# Decoder.net
KiCad netlist of a schematic drawn in EAGLE
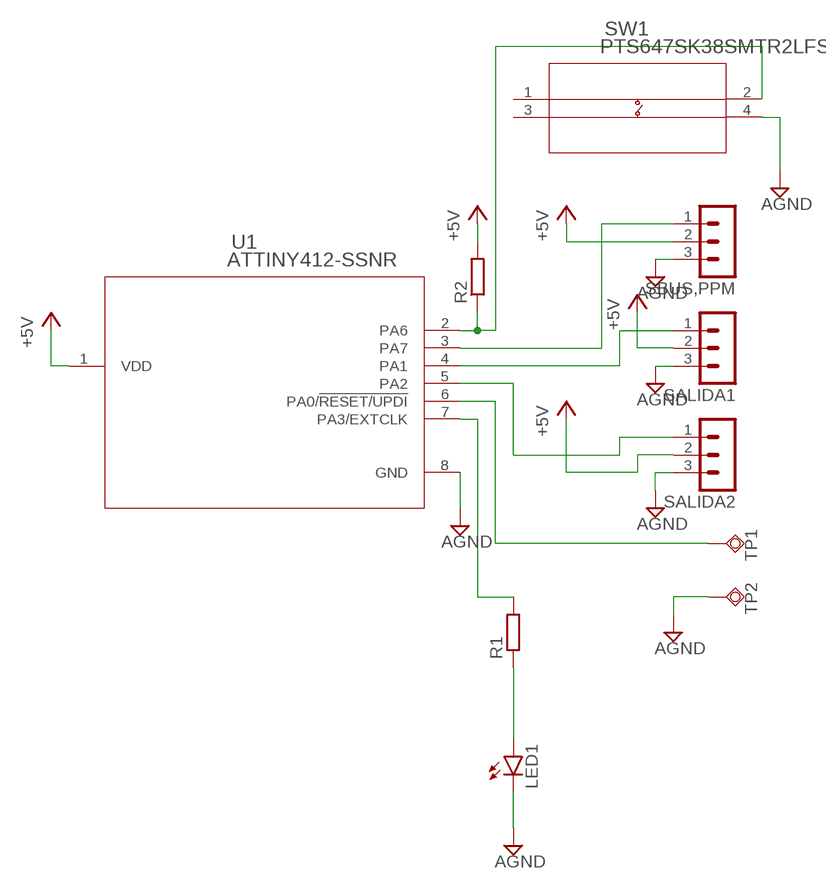
[diagram p0: schematic, sheet 1]

(export (version "E")
  (design (tool "Eeschema 10.0.6"))
  (components
    (comp (ref "LED1")
      (value "LEDCHIPLED_0603")
      (footprint "eagle-import:CHIPLED_0603")
      (libsource (lib "eagle-import") (part "LEDCHIPLED_0603"))
    )
    (comp (ref "R1")
      (value "R-EU_R0805")
      (footprint "eagle-import:R0805")
      (libsource (lib "eagle-import") (part "R-EU_R0805"))
    )
    (comp (ref "R2")
      (value "R-EU_R0805")
      (footprint "eagle-import:R0805")
      (libsource (lib "eagle-import") (part "R-EU_R0805"))
    )
    (comp (ref "SALIDA1")
      (value "MA03-1")
      (footprint "eagle-import:MA03-1")
      (libsource (lib "eagle-import") (part "MA03-1"))
    )
    (comp (ref "SALIDA2")
      (value "MA03-1")
      (footprint "eagle-import:MA03-1")
      (libsource (lib "eagle-import") (part "MA03-1"))
    )
    (comp (ref "SBUS,PPM")
      (value "MA03-1")
      (footprint "eagle-import:MA03-1")
      (libsource (lib "eagle-import") (part "MA03-1"))
    )
    (comp (ref "SW1")
      (value "PTS647SK38SMTR2LFS")
      (footprint "eagle-import:PTS647SK38SMTR2LFS_CNK")
      (fields (field (name "COPYRIGHT") "Copyright (C) 2018 Accelerated Designs. All rights reserved"))
      (libsource (lib "eagle-import") (part "PTS647SK38SMTR2LFS"))
    )
    (comp (ref "TP1")
      (value "TPSQTP13R")
      (footprint "eagle-import:TP13R")
      (libsource (lib "eagle-import") (part "TPSQTP13R"))
    )
    (comp (ref "TP2")
      (value "TPSQTP13R")
      (footprint "eagle-import:TP13R")
      (libsource (lib "eagle-import") (part "TPSQTP13R"))
    )
    (comp (ref "U1")
      (value "ATTINY412-SSNR")
      (footprint "eagle-import:SOIC8_SA_SST_MCH")
      (fields (field (name "COPYRIGHT") "Copyright (C) 2018 Accelerated Designs. All rights reserved"))
      (libsource (lib "eagle-import") (part "ATTINY412-SSNR"))
    )
  )
  (nets
    (net (code "1") (name "+5V") (class "Default")
      (node (ref "R2") (pin "2") (pinfunction "2_2") (pintype "passive"))
      (node (ref "SALIDA1") (pin "2") (pinfunction "2_2") (pintype "passive"))
      (node (ref "SALIDA2") (pin "2") (pinfunction "2_2") (pintype "passive"))
      (node (ref "SBUS,PPM") (pin "2") (pinfunction "2_2") (pintype "passive"))
      (node (ref "U1") (pin "1") (pinfunction "VDD_1") (pintype "power_in"))
    )
    (net (code "2") (name "AGND") (class "Default")
      (node (ref "LED1") (pin "C") (pinfunction "C_C") (pintype "passive"))
      (node (ref "SALIDA1") (pin "3") (pinfunction "3_3") (pintype "passive"))
      (node (ref "SALIDA2") (pin "3") (pinfunction "3_3") (pintype "passive"))
      (node (ref "SBUS,PPM") (pin "3") (pinfunction "3_3") (pintype "passive"))
      (node (ref "SW1") (pin "4") (pinfunction "4_4") (pintype "passive"))
      (node (ref "TP2") (pin "TP") (pinfunction "TP_TP") (pintype "input"))
      (node (ref "U1") (pin "8") (pinfunction "GND_8") (pintype "passive"))
    )
    (net (code "3") (name "Net-(LED1-PadA)") (class "Default")
      (node (ref "LED1") (pin "A") (pinfunction "A_A") (pintype "passive"))
      (node (ref "R1") (pin "1") (pinfunction "1_1") (pintype "passive"))
    )
    (net (code "4") (name "Net-(U1-PA0{slash}~{RESET{slash}UPDI})") (class "Default")
      (node (ref "TP1") (pin "TP") (pinfunction "TP_TP") (pintype "input"))
      (node (ref "U1") (pin "6") (pinfunction "PA0/~{RESET/UPDI}_6") (pintype "bidirectional"))
    )
    (net (code "5") (name "Net-(U1-PA1)") (class "Default")
      (node (ref "SALIDA1") (pin "1") (pinfunction "1_1") (pintype "passive"))
      (node (ref "U1") (pin "4") (pinfunction "PA1_4") (pintype "bidirectional"))
    )
    (net (code "6") (name "Net-(U1-PA2)") (class "Default")
      (node (ref "SALIDA2") (pin "1") (pinfunction "1_1") (pintype "passive"))
      (node (ref "U1") (pin "5") (pinfunction "PA2_5") (pintype "bidirectional"))
    )
    (net (code "7") (name "Net-(U1-PA3{slash}EXTCLK)") (class "Default")
      (node (ref "R1") (pin "2") (pinfunction "2_2") (pintype "passive"))
      (node (ref "U1") (pin "7") (pinfunction "PA3/EXTCLK_7") (pintype "bidirectional"))
    )
    (net (code "8") (name "Net-(U1-PA6)") (class "Default")
      (node (ref "R2") (pin "1") (pinfunction "1_1") (pintype "passive"))
      (node (ref "SW1") (pin "2") (pinfunction "2_2") (pintype "passive"))
      (node (ref "U1") (pin "2") (pinfunction "PA6_2") (pintype "bidirectional"))
    )
    (net (code "9") (name "Net-(U1-PA7)") (class "Default")
      (node (ref "SBUS,PPM") (pin "1") (pinfunction "1_1") (pintype "passive"))
      (node (ref "U1") (pin "3") (pinfunction "PA7_3") (pintype "bidirectional"))
    )
    (net (code "10") (name "unconnected-(SW1-Pad1)") (class "Default")
      (node (ref "SW1") (pin "1") (pinfunction "1_1") (pintype "passive"))
    )
    (net (code "11") (name "unconnected-(SW1-Pad3)") (class "Default")
      (node (ref "SW1") (pin "3") (pinfunction "3_3") (pintype "passive"))
    )
  )
)
